# flyback_sematik.net
KiCad netlist of a schematic drawn in Altium Designer
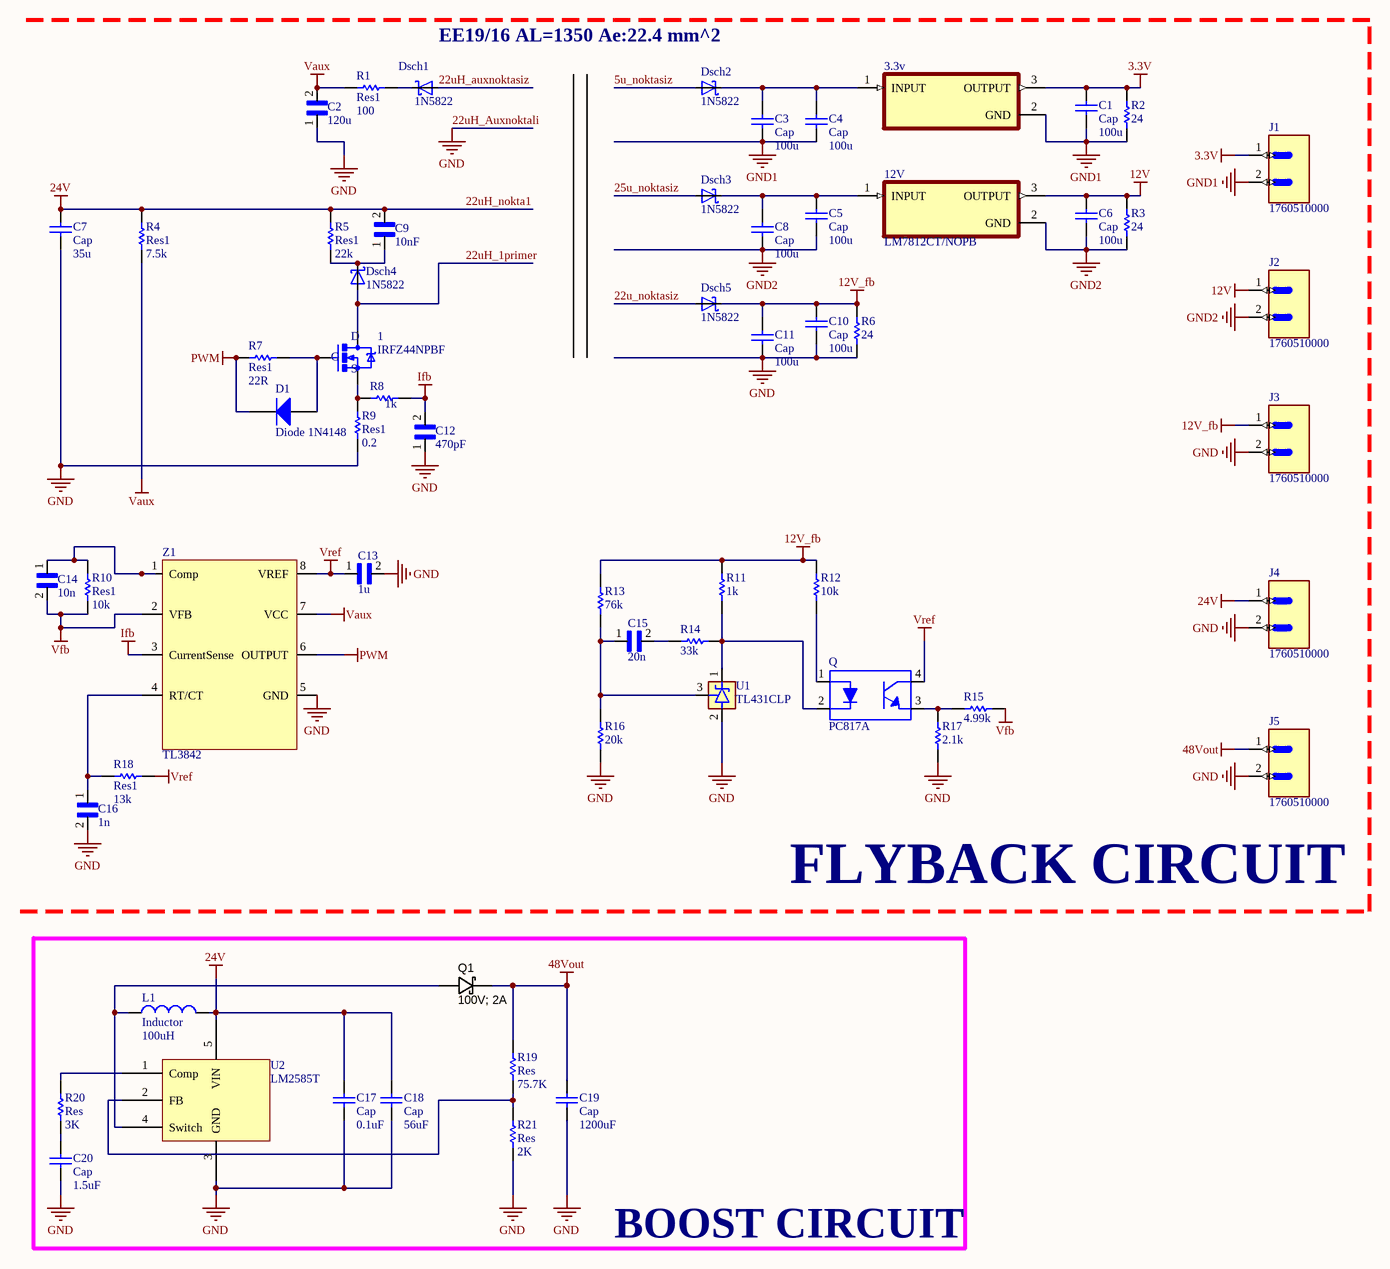
[diagram p0: flyback_sematik.SchDoc]

(export (version "E")
  (design (tool "Eeschema 10.0.6"))
  (components
    (comp (ref "1")
      (value "IRFZ44NPBF")
      (footprint "TO-220")
      (fields (field (name "MF") "Infineon"))
      (libsource (lib "IRFZ44NPBF") (part "IRFZ44NPBF"))
    )
    (comp (ref "3.3v")
      (value "LM7812CT/NOPB")
      (footprint "TO254P1054X470X1955-3")
      (description "1.5-A, 30-V, linear voltage regulator 3-TO-220 -40 to 125")
      (fields (field (name "MF") "Texas Instruments"))
      (libsource (lib "LM7812CT_NOPB") (part "LM7812CT/NOPB"))
    )
    (comp (ref "12V")
      (value "LM7812CT/NOPB")
      (footprint "TO254P1054X470X1955-3")
      (description "1.5-A, 30-V, linear voltage regulator 3-TO-220 -40 to 125")
      (fields (field (name "MF") "Texas Instruments"))
      (libsource (lib "LM7812CT_NOPB") (part "LM7812CT/NOPB"))
    )
    (comp (ref "C1")
      (value "Cap")
      (footprint "Cap1")
      (description "Capacitor")
      (fields (field (name "ALTIUM_VALUE") "100u") (field (name "PUBLISHER") "Altium Limited"))
      (libsource (lib "Miscellaneous Devices") (part "Cap"))
    )
    (comp (ref "C2")
      (value "120u")
      (footprint "CAP_RCER72A472K0A2H03B")
      (description "Cap Ceramic 1pF 50V C0G 0.25pF Radial 2.5mm 125C Automotive Bulk")
      (fields (field (name "MP") "RCER72A472K0A2H03B"))
      (libsource (lib "") (part "RCER72A472K0A2H03B_1"))
    )
    (comp (ref "C3")
      (value "Cap")
      (footprint "Cap1")
      (description "Capacitor")
      (fields (field (name "ALTIUM_VALUE") "100u") (field (name "PUBLISHER") "Altium Limited"))
      (libsource (lib "Miscellaneous Devices") (part "Cap"))
    )
    (comp (ref "C4")
      (value "Cap")
      (footprint "Cap1")
      (description "Capacitor")
      (fields (field (name "ALTIUM_VALUE") "100u") (field (name "PUBLISHER") "Altium Limited"))
      (libsource (lib "Miscellaneous Devices") (part "Cap"))
    )
    (comp (ref "C5")
      (value "Cap")
      (footprint "Cap1")
      (description "Capacitor")
      (fields (field (name "ALTIUM_VALUE") "100u") (field (name "PUBLISHER") "Altium Limited"))
      (libsource (lib "Miscellaneous Devices") (part "Cap"))
    )
    (comp (ref "C6")
      (value "Cap")
      (footprint "Cap1")
      (description "Capacitor")
      (fields (field (name "ALTIUM_VALUE") "100u") (field (name "PUBLISHER") "Altium Limited"))
      (libsource (lib "Miscellaneous Devices") (part "Cap"))
    )
    (comp (ref "C7")
      (value "Cap")
      (footprint "Cap1")
      (description "Capacitor")
      (fields (field (name "ALTIUM_VALUE") "35u") (field (name "PUBLISHER") "Altium Limited"))
      (libsource (lib "Miscellaneous Devices") (part "Cap"))
    )
    (comp (ref "C8")
      (value "Cap")
      (footprint "Cap1")
      (description "Capacitor")
      (fields (field (name "ALTIUM_VALUE") "100u") (field (name "PUBLISHER") "Altium Limited"))
      (libsource (lib "Miscellaneous Devices") (part "Cap"))
    )
    (comp (ref "C9")
      (value "10nF")
      (footprint "CAP_RCER72A472K0A2H03B")
      (description "Cap Ceramic 1pF 50V C0G 0.25pF Radial 2.5mm 125C Automotive Bulk")
      (fields (field (name "MP") "RCER72A472K0A2H03B"))
      (libsource (lib "") (part "RCER72A472K0A2H03B_1"))
    )
    (comp (ref "C10")
      (value "Cap")
      (footprint "Cap1")
      (description "Capacitor")
      (fields (field (name "ALTIUM_VALUE") "100u") (field (name "PUBLISHER") "Altium Limited"))
      (libsource (lib "Miscellaneous Devices") (part "Cap"))
    )
    (comp (ref "C11")
      (value "Cap")
      (footprint "Cap1")
      (description "Capacitor")
      (fields (field (name "ALTIUM_VALUE") "100u") (field (name "PUBLISHER") "Altium Limited"))
      (libsource (lib "Miscellaneous Devices") (part "Cap"))
    )
    (comp (ref "C12")
      (value "470pF")
      (footprint "CAP_RCER72A472K0A2H03B")
      (description "Cap Ceramic 1pF 50V C0G 0.25pF Radial 2.5mm 125C Automotive Bulk")
      (fields (field (name "MP") "RCER72A472K0A2H03B"))
      (libsource (lib "") (part "RCER72A472K0A2H03B_1"))
    )
    (comp (ref "C13")
      (value "1u")
      (footprint "CAP_RCER72A472K0A2H03B")
      (description "Cap Ceramic 1pF 50V C0G 0.25pF Radial 2.5mm 125C Automotive Bulk")
      (fields (field (name "MP") "RCER72A472K0A2H03B"))
      (libsource (lib "RCER72A472K0A2H03B") (part "RCER72A472K0A2H03B"))
    )
    (comp (ref "C14")
      (value "10n")
      (footprint "CAP_RCER72A472K0A2H03B")
      (description "Cap Ceramic 1pF 50V C0G 0.25pF Radial 2.5mm 125C Automotive Bulk")
      (fields (field (name "MP") "RCER72A472K0A2H03B"))
      (libsource (lib "") (part "RCER72A472K0A2H03B_2"))
    )
    (comp (ref "C15")
      (value "20n")
      (footprint "CAP_RCER72A472K0A2H03B")
      (description "Cap Ceramic 1pF 50V C0G 0.25pF Radial 2.5mm 125C Automotive Bulk")
      (fields (field (name "MP") "RCER72A472K0A2H03B"))
      (libsource (lib "RCER72A472K0A2H03B") (part "RCER72A472K0A2H03B"))
    )
    (comp (ref "C16")
      (value "1n")
      (footprint "CAP_RCER72A472K0A2H03B")
      (description "Cap Ceramic 1pF 50V C0G 0.25pF Radial 2.5mm 125C Automotive Bulk")
      (fields (field (name "MP") "RCER72A472K0A2H03B"))
      (libsource (lib "") (part "RCER72A472K0A2H03B_2"))
    )
    (comp (ref "C17")
      (value "Cap")
      (footprint "Cap1")
      (description "Capacitor")
      (fields (field (name "ALTIUM_VALUE") "0.1uF") (field (name "PUBLISHER") "Altium Limited"))
      (libsource (lib "Miscellaneous Devices") (part "Cap"))
    )
    (comp (ref "C18")
      (value "Cap")
      (footprint "Cap1")
      (description "Capacitor")
      (fields (field (name "ALTIUM_VALUE") "56uF") (field (name "PUBLISHER") "Altium Limited"))
      (libsource (lib "Miscellaneous Devices") (part "Cap"))
    )
    (comp (ref "C19")
      (value "Cap")
      (footprint "Cap1")
      (description "Capacitor")
      (fields (field (name "ALTIUM_VALUE") "1200uF") (field (name "PUBLISHER") "Altium Limited"))
      (libsource (lib "Miscellaneous Devices") (part "Cap"))
    )
    (comp (ref "C20")
      (value "Cap")
      (footprint "Cap1")
      (description "Capacitor")
      (fields (field (name "ALTIUM_VALUE") "1.5uF") (field (name "PUBLISHER") "Altium Limited"))
      (libsource (lib "Miscellaneous Devices") (part "Cap"))
    )
    (comp (ref "D1")
      (value "Diode 1N4148")
      (footprint "DO-35")
      (description "High Conductance Fast Diode")
      (fields (field (name "PUBLISHER") "Altium Limited"))
      (libsource (lib "Miscellaneous Devices") (part "Diode 1N4148"))
    )
    (comp (ref "Dsch1")
      (value "1N5822")
      (footprint "DIOAD2120W130L950D530P")
      (description "Diode Schottky 40V 3A Through Hole")
      (fields (field (name "MF") "ON Semiconductor"))
      (libsource (lib "1N5822") (part "1N5822"))
    )
    (comp (ref "Dsch2")
      (value "1N5822")
      (footprint "DIOAD2120W130L950D530P")
      (description "Diode Schottky 40V 3A Through Hole")
      (fields (field (name "MF") "ON Semiconductor"))
      (libsource (lib "1N5822") (part "1N5822"))
    )
    (comp (ref "Dsch3")
      (value "1N5822")
      (footprint "DIOAD2120W130L950D530P")
      (description "Diode Schottky 40V 3A Through Hole")
      (fields (field (name "MF") "ON Semiconductor"))
      (libsource (lib "1N5822") (part "1N5822"))
    )
    (comp (ref "Dsch4")
      (value "1N5822")
      (footprint "DIOAD2120W130L950D530P")
      (description "Diode Schottky 40V 3A Through Hole")
      (fields (field (name "MF") "ON Semiconductor"))
      (libsource (lib "1N5822") (part "1N5822"))
    )
    (comp (ref "Dsch5")
      (value "1N5822")
      (footprint "DIOAD2120W130L950D530P")
      (description "Diode Schottky 40V 3A Through Hole")
      (fields (field (name "MF") "ON Semiconductor"))
      (libsource (lib "1N5822") (part "1N5822"))
    )
    (comp (ref "J1")
      (value "1760510000")
      (footprint "1760490000")
      (description "2 Position Wire to Board Terminal Block Horizontal with Board 0.200 _5.08mm_ Through Hole")
      (fields (field (name "MF") "Weidmuller"))
      (libsource (lib "1760510000") (part "1760510000"))
    )
    (comp (ref "J2")
      (value "1760510000")
      (footprint "1760490000")
      (description "2 Position Wire to Board Terminal Block Horizontal with Board 0.200 _5.08mm_ Through Hole")
      (fields (field (name "MF") "Weidmuller"))
      (libsource (lib "1760510000") (part "1760510000"))
    )
    (comp (ref "J3")
      (value "1760510000")
      (footprint "1760490000")
      (description "2 Position Wire to Board Terminal Block Horizontal with Board 0.200 _5.08mm_ Through Hole")
      (fields (field (name "MF") "Weidmuller"))
      (libsource (lib "1760510000") (part "1760510000"))
    )
    (comp (ref "J4")
      (value "1760510000")
      (footprint "1760490000")
      (description "2 Position Wire to Board Terminal Block Horizontal with Board 0.200 _5.08mm_ Through Hole")
      (fields (field (name "MF") "Weidmuller"))
      (libsource (lib "1760510000") (part "1760510000"))
    )
    (comp (ref "J5")
      (value "1760510000")
      (footprint "1760490000")
      (description "2 Position Wire to Board Terminal Block Horizontal with Board 0.200 _5.08mm_ Through Hole")
      (fields (field (name "MF") "Weidmuller"))
      (libsource (lib "1760510000") (part "1760510000"))
    )
    (comp (ref "L1")
      (value "Inductor")
      (footprint "Inductor2")
      (fields (field (name "ALTIUM_VALUE") "100uH") (field (name "PUBLISHER") "Altium Limited"))
      (libsource (lib "Miscellaneous Devices") (part "Inductor"))
    )
    (comp (ref "Q")
      (value "PC817A")
      (footprint "DIP762W50P254L650H458Q4B")
      (description "Optoisolator Transistor Output 5000Vrms 1 Channel 4-DIP")
      (fields (field (name "MF") "Taiwan Semiconductor"))
      (libsource (lib "PC817A") (part "PC817A"))
    )
    (comp (ref "Q1")
      (value "DIODE_SCHOTTKY_10MQ100NPBF")
      (footprint "Schottky")
      (description "Diode Schottky SMD 100V 2A SMA")
      (fields (field (name "RATINGS") "100V; 2A"))
      (libsource (lib "PBL - Diodes") (part "DIODE_SCHOTTKY_10MQ100NPBF"))
    )
    (comp (ref "R1")
      (value "Res1")
      (footprint "AXIAL-0.3")
      (description "Resistor")
      (fields (field (name "ALTIUM_VALUE") "100") (field (name "PUBLISHER") "Altium Limited"))
      (libsource (lib "Miscellaneous Devices") (part "Res1"))
    )
    (comp (ref "R2")
      (value "24")
      (footprint "AXIAL-0.3")
      (description "Resistor")
      (fields (field (name "Comment") "Res1") (field (name "PUBLISHER") "Altium Limited"))
      (libsource (lib "Miscellaneous Devices") (part "Res1"))
    )
    (comp (ref "R3")
      (value "24")
      (footprint "AXIAL-0.3")
      (description "Resistor")
      (fields (field (name "Comment") "Res1") (field (name "PUBLISHER") "Altium Limited"))
      (libsource (lib "Miscellaneous Devices") (part "Res1"))
    )
    (comp (ref "R4")
      (value "Res1")
      (footprint "AXIAL-0.3")
      (description "Resistor")
      (fields (field (name "ALTIUM_VALUE") "7.5k") (field (name "PUBLISHER") "Altium Limited"))
      (libsource (lib "Miscellaneous Devices") (part "Res1"))
    )
    (comp (ref "R5")
      (value "Res1")
      (footprint "AXIAL-0.3")
      (description "Resistor")
      (fields (field (name "ALTIUM_VALUE") "22k") (field (name "PUBLISHER") "Altium Limited"))
      (libsource (lib "Miscellaneous Devices") (part "Res1"))
    )
    (comp (ref "R6")
      (value "24")
      (footprint "AXIAL-0.3")
      (description "Resistor")
      (fields (field (name "Comment") "Res1") (field (name "PUBLISHER") "Altium Limited"))
      (libsource (lib "Miscellaneous Devices") (part "Res1"))
    )
    (comp (ref "R7")
      (value "Res1")
      (footprint "AXIAL-0.3")
      (description "Resistor")
      (fields (field (name "ALTIUM_VALUE") "22R") (field (name "PUBLISHER") "Altium Limited"))
      (libsource (lib "Miscellaneous Devices") (part "Res1"))
    )
    (comp (ref "R8")
      (value "1k")
      (footprint "AXIAL-0.3")
      (description "Resistor")
      (fields (field (name "Comment") "Res1") (field (name "PUBLISHER") "Altium Limited"))
      (libsource (lib "Miscellaneous Devices") (part "Res1"))
    )
    (comp (ref "R9")
      (value "Res1")
      (footprint "AXIAL-0.3")
      (description "Resistor")
      (fields (field (name "ALTIUM_VALUE") "0.2") (field (name "PUBLISHER") "Altium Limited"))
      (libsource (lib "Miscellaneous Devices") (part "Res1"))
    )
    (comp (ref "R10")
      (value "Res1")
      (footprint "AXIAL-0.3")
      (description "Resistor")
      (fields (field (name "ALTIUM_VALUE") "10k") (field (name "PUBLISHER") "Altium Limited"))
      (libsource (lib "Miscellaneous Devices") (part "Res1"))
    )
    (comp (ref "R11")
      (value "1k")
      (footprint "AXIAL-0.3")
      (description "Resistor")
      (fields (field (name "Comment") "Res1") (field (name "PUBLISHER") "Altium Limited"))
      (libsource (lib "Miscellaneous Devices") (part "Res1"))
    )
    (comp (ref "R12")
      (value "10k")
      (footprint "AXIAL-0.3")
      (description "Resistor")
      (fields (field (name "Comment") "Res1") (field (name "PUBLISHER") "Altium Limited"))
      (libsource (lib "Miscellaneous Devices") (part "Res1"))
    )
    (comp (ref "R13")
      (value "76k")
      (footprint "AXIAL-0.3")
      (description "Resistor")
      (fields (field (name "Comment") "Res1") (field (name "PUBLISHER") "Altium Limited"))
      (libsource (lib "Miscellaneous Devices") (part "Res1"))
    )
    (comp (ref "R14")
      (value "33k")
      (footprint "AXIAL-0.3")
      (description "Resistor")
      (fields (field (name "Comment") "Res1") (field (name "PUBLISHER") "Altium Limited"))
      (libsource (lib "Miscellaneous Devices") (part "Res1"))
    )
    (comp (ref "R15")
      (value "4.99k")
      (footprint "AXIAL-0.3")
      (description "Resistor")
      (fields (field (name "Comment") "Res1") (field (name "PUBLISHER") "Altium Limited"))
      (libsource (lib "Miscellaneous Devices") (part "Res1"))
    )
    (comp (ref "R16")
      (value "20k")
      (footprint "AXIAL-0.3")
      (description "Resistor")
      (fields (field (name "Comment") "Res1") (field (name "PUBLISHER") "Altium Limited"))
      (libsource (lib "Miscellaneous Devices") (part "Res1"))
    )
    (comp (ref "R17")
      (value "2.1k")
      (footprint "AXIAL-0.3")
      (description "Resistor")
      (fields (field (name "Comment") "Res1") (field (name "PUBLISHER") "Altium Limited"))
      (libsource (lib "Miscellaneous Devices") (part "Res1"))
    )
    (comp (ref "R18")
      (value "Res1")
      (footprint "AXIAL-0.3")
      (description "Resistor")
      (fields (field (name "ALTIUM_VALUE") "13k") (field (name "PUBLISHER") "Altium Limited"))
      (libsource (lib "Miscellaneous Devices") (part "Res1"))
    )
    (comp (ref "R19")
      (value "Res")
      (footprint "AXIAL-0.3")
      (description "Resistor")
      (fields (field (name "ALTIUM_VALUE") "75.7K") (field (name "PUBLISHER") "Altium Limited"))
      (libsource (lib "Miscellaneous Devices") (part "Res1"))
    )
    (comp (ref "R20")
      (value "Res")
      (footprint "AXIAL-0.3")
      (description "Resistor")
      (fields (field (name "ALTIUM_VALUE") "3K") (field (name "PUBLISHER") "Altium Limited"))
      (libsource (lib "Miscellaneous Devices") (part "Res1"))
    )
    (comp (ref "R21")
      (value "Res")
      (footprint "AXIAL-0.3")
      (description "Resistor")
      (fields (field (name "ALTIUM_VALUE") "2K") (field (name "PUBLISHER") "Altium Limited"))
      (libsource (lib "Miscellaneous Devices") (part "Res1"))
    )
    (comp (ref "U1")
      (value "TL431CLP")
      (footprint "TO-92")
      (description "Adjustable precision shunt regulator 3-TO-92 0 to 70")
      (fields (field (name "MF") "Texas Instruments"))
      (libsource (lib "TL431CLP") (part "TL431CLP"))
    )
    (comp (ref "U2") (value "LM2585T") (footprint "LM2585T") (libsource (lib "LM2585T") (part "LM2585T")))
    (comp (ref "Z1")
      (value "TL3842")
      (footprint "TL3842_PCBLIB")
      (libsource (lib "TL3842_schematicLib") (part "TL3842"))
    )
  )
  (nets
    (net (code "1") (name "/5u_noktasiz") (class "Default")
      (node (ref "Dsch2") (pin "A") (pinfunction "A_A") (pintype "passive"))
    )
    (net (code "2") (name "/22uH_1primer") (class "Default")
      (node (ref "1") (pin "2") (pinfunction "D_2") (pintype "passive"))
      (node (ref "Dsch4") (pin "A") (pinfunction "A_A") (pintype "passive"))
    )
    (net (code "3") (name "/22uH_auxnoktasiz") (class "Default")
      (node (ref "Dsch1") (pin "A") (pinfunction "A_A") (pintype "passive"))
    )
    (net (code "4") (name "/22u_noktasiz") (class "Default")
      (node (ref "Dsch5") (pin "A") (pinfunction "A_A") (pintype "passive"))
    )
    (net (code "5") (name "/25u_noktasiz") (class "Default")
      (node (ref "Dsch3") (pin "A") (pinfunction "A_A") (pintype "passive"))
    )
    (net (code "6") (name "3.3V") (class "Default")
      (node (ref "3.3v") (pin "3") (pinfunction "OUTPUT_3") (pintype "output"))
      (node (ref "C1") (pin "1") (pinfunction "1_1") (pintype "passive"))
      (node (ref "J1") (pin "1") (pinfunction "1_1") (pintype "bidirectional"))
      (node (ref "R2") (pin "2") (pinfunction "2_2") (pintype "passive"))
    )
    (net (code "7") (name "12V") (class "Default")
      (node (ref "12V") (pin "3") (pinfunction "OUTPUT_3") (pintype "output"))
      (node (ref "C6") (pin "1") (pinfunction "1_1") (pintype "passive"))
      (node (ref "J2") (pin "1") (pinfunction "1_1") (pintype "bidirectional"))
      (node (ref "R3") (pin "2") (pinfunction "2_2") (pintype "passive"))
    )
    (net (code "8") (name "12V_fb") (class "Default")
      (node (ref "C10") (pin "1") (pinfunction "1_1") (pintype "passive"))
      (node (ref "C11") (pin "1") (pinfunction "1_1") (pintype "passive"))
      (node (ref "Dsch5") (pin "C") (pinfunction "C_C") (pintype "passive"))
      (node (ref "J3") (pin "1") (pinfunction "1_1") (pintype "bidirectional"))
      (node (ref "R11") (pin "2") (pinfunction "2_2") (pintype "passive"))
      (node (ref "R12") (pin "2") (pinfunction "2_2") (pintype "passive"))
      (node (ref "R13") (pin "2") (pinfunction "2_2") (pintype "passive"))
      (node (ref "R6") (pin "2") (pinfunction "2_2") (pintype "passive"))
    )
    (net (code "9") (name "24V") (class "Default")
      (node (ref "C17") (pin "1") (pinfunction "1_1") (pintype "passive"))
      (node (ref "C18") (pin "1") (pinfunction "1_1") (pintype "passive"))
      (node (ref "C7") (pin "1") (pinfunction "1_1") (pintype "passive"))
      (node (ref "C9") (pin "2") (pinfunction "2_2") (pintype "passive"))
      (node (ref "J4") (pin "1") (pinfunction "1_1") (pintype "bidirectional"))
      (node (ref "L1") (pin "2") (pinfunction "2_2") (pintype "passive"))
      (node (ref "R4") (pin "1") (pinfunction "1_1") (pintype "passive"))
      (node (ref "R5") (pin "1") (pinfunction "1_1") (pintype "passive"))
      (node (ref "U2") (pin "5") (pinfunction "VIN_5") (pintype "passive"))
    )
    (net (code "10") (name "48Vout") (class "Default")
      (node (ref "C19") (pin "1") (pinfunction "1_1") (pintype "passive"))
      (node (ref "J5") (pin "1") (pinfunction "1_1") (pintype "bidirectional"))
      (node (ref "Q1") (pin "2") (pinfunction "2_2") (pintype "passive"))
      (node (ref "R19") (pin "2") (pinfunction "2_2") (pintype "passive"))
    )
    (net (code "11") (name "GND") (class "Default")
      (node (ref "C10") (pin "2") (pinfunction "2_2") (pintype "passive"))
      (node (ref "C11") (pin "2") (pinfunction "2_2") (pintype "passive"))
      (node (ref "C12") (pin "1") (pinfunction "1_1") (pintype "passive"))
      (node (ref "C13") (pin "2") (pinfunction "2_2") (pintype "passive"))
      (node (ref "C16") (pin "2") (pinfunction "2_2") (pintype "passive"))
      (node (ref "C17") (pin "2") (pinfunction "2_2") (pintype "passive"))
      (node (ref "C18") (pin "2") (pinfunction "2_2") (pintype "passive"))
      (node (ref "C19") (pin "2") (pinfunction "2_2") (pintype "passive"))
      (node (ref "C2") (pin "1") (pinfunction "1_1") (pintype "passive"))
      (node (ref "C20") (pin "2") (pinfunction "2_2") (pintype "passive"))
      (node (ref "C7") (pin "2") (pinfunction "2_2") (pintype "passive"))
      (node (ref "J3") (pin "2") (pinfunction "2_2") (pintype "bidirectional"))
      (node (ref "J4") (pin "2") (pinfunction "2_2") (pintype "bidirectional"))
      (node (ref "J5") (pin "2") (pinfunction "2_2") (pintype "bidirectional"))
      (node (ref "R16") (pin "1") (pinfunction "1_1") (pintype "passive"))
      (node (ref "R17") (pin "2") (pinfunction "2_2") (pintype "passive"))
      (node (ref "R21") (pin "1") (pinfunction "1_1") (pintype "passive"))
      (node (ref "R6") (pin "1") (pinfunction "1_1") (pintype "passive"))
      (node (ref "R9") (pin "2") (pinfunction "2_2") (pintype "passive"))
      (node (ref "U1") (pin "2") (pinfunction "ANODE_2") (pintype "passive"))
      (node (ref "U2") (pin "3") (pinfunction "GND_3") (pintype "passive"))
      (node (ref "Z1") (pin "5") (pinfunction "GND_5") (pintype "passive"))
    )
    (net (code "12") (name "GND1") (class "Default")
      (node (ref "3.3v") (pin "2") (pinfunction "GND_2") (pintype "power_in"))
      (node (ref "C1") (pin "2") (pinfunction "2_2") (pintype "passive"))
      (node (ref "C3") (pin "2") (pinfunction "2_2") (pintype "passive"))
      (node (ref "C4") (pin "2") (pinfunction "2_2") (pintype "passive"))
      (node (ref "J1") (pin "2") (pinfunction "2_2") (pintype "bidirectional"))
      (node (ref "R2") (pin "1") (pinfunction "1_1") (pintype "passive"))
    )
    (net (code "13") (name "GND2") (class "Default")
      (node (ref "12V") (pin "2") (pinfunction "GND_2") (pintype "power_in"))
      (node (ref "C5") (pin "2") (pinfunction "2_2") (pintype "passive"))
      (node (ref "C6") (pin "2") (pinfunction "2_2") (pintype "passive"))
      (node (ref "C8") (pin "2") (pinfunction "2_2") (pintype "passive"))
      (node (ref "J2") (pin "2") (pinfunction "2_2") (pintype "bidirectional"))
      (node (ref "R3") (pin "1") (pinfunction "1_1") (pintype "passive"))
    )
    (net (code "14") (name "Ifb") (class "Default")
      (node (ref "C12") (pin "2") (pinfunction "2_2") (pintype "passive"))
      (node (ref "R8") (pin "2") (pinfunction "2_2") (pintype "passive"))
      (node (ref "Z1") (pin "3") (pinfunction "CurrentSense_3") (pintype "passive"))
    )
    (net (code "15") (name "Net-(1-G)") (class "Default")
      (node (ref "1") (pin "1") (pinfunction "G_1") (pintype "passive"))
      (node (ref "D1") (pin "1") (pinfunction "A_1") (pintype "passive"))
      (node (ref "R7") (pin "2") (pinfunction "2_2") (pintype "passive"))
    )
    (net (code "16") (name "Net-(1-S)") (class "Default")
      (node (ref "1") (pin "3") (pinfunction "S_3") (pintype "passive"))
      (node (ref "R8") (pin "1") (pinfunction "1_1") (pintype "passive"))
      (node (ref "R9") (pin "1") (pinfunction "1_1") (pintype "passive"))
    )
    (net (code "17") (name "Net-(3.3v-INPUT)") (class "Default")
      (node (ref "3.3v") (pin "1") (pinfunction "INPUT_1") (pintype "input"))
      (node (ref "C3") (pin "1") (pinfunction "1_1") (pintype "passive"))
      (node (ref "C4") (pin "1") (pinfunction "1_1") (pintype "passive"))
      (node (ref "Dsch2") (pin "C") (pinfunction "C_C") (pintype "passive"))
    )
    (net (code "18") (name "Net-(12V-INPUT)") (class "Default")
      (node (ref "12V") (pin "1") (pinfunction "INPUT_1") (pintype "input"))
      (node (ref "C5") (pin "1") (pinfunction "1_1") (pintype "passive"))
      (node (ref "C8") (pin "1") (pinfunction "1_1") (pintype "passive"))
      (node (ref "Dsch3") (pin "C") (pinfunction "C_C") (pintype "passive"))
    )
    (net (code "19") (name "Net-(C9-Pad1)") (class "Default")
      (node (ref "C9") (pin "1") (pinfunction "1_1") (pintype "passive"))
      (node (ref "Dsch4") (pin "C") (pinfunction "C_C") (pintype "passive"))
      (node (ref "R5") (pin "2") (pinfunction "2_2") (pintype "passive"))
    )
    (net (code "20") (name "Net-(C15-Pad2)") (class "Default")
      (node (ref "C15") (pin "2") (pinfunction "2_2") (pintype "passive"))
      (node (ref "R14") (pin "2") (pinfunction "2_2") (pintype "passive"))
    )
    (net (code "21") (name "Net-(C20-Pad1)") (class "Default")
      (node (ref "C20") (pin "1") (pinfunction "1_1") (pintype "passive"))
      (node (ref "R20") (pin "1") (pinfunction "1_1") (pintype "passive"))
    )
    (net (code "22") (name "Net-(Dsch1-PadC)") (class "Default")
      (node (ref "Dsch1") (pin "C") (pinfunction "C_C") (pintype "passive"))
      (node (ref "R1") (pin "1") (pinfunction "1_1") (pintype "passive"))
    )
    (net (code "23") (name "Net-(Q-Pad1)") (class "Default")
      (node (ref "Q") (pin "1") (pinfunction "1_1") (pintype "passive"))
      (node (ref "R12") (pin "1") (pinfunction "1_1") (pintype "passive"))
    )
    (net (code "24") (name "Net-(Q-Pad3)") (class "Default")
      (node (ref "Q") (pin "3") (pinfunction "3_3") (pintype "passive"))
      (node (ref "R15") (pin "2") (pinfunction "2_2") (pintype "passive"))
      (node (ref "R17") (pin "1") (pinfunction "1_1") (pintype "passive"))
    )
    (net (code "25") (name "Net-(U1-CATHODE)") (class "Default")
      (node (ref "Q") (pin "2") (pinfunction "2_2") (pintype "passive"))
      (node (ref "R11") (pin "1") (pinfunction "1_1") (pintype "passive"))
      (node (ref "R14") (pin "1") (pinfunction "1_1") (pintype "passive"))
      (node (ref "U1") (pin "1") (pinfunction "CATHODE_1") (pintype "passive"))
    )
    (net (code "26") (name "Net-(U1-REF)") (class "Default")
      (node (ref "C15") (pin "1") (pinfunction "1_1") (pintype "passive"))
      (node (ref "R13") (pin "1") (pinfunction "1_1") (pintype "passive"))
      (node (ref "R16") (pin "2") (pinfunction "2_2") (pintype "passive"))
      (node (ref "U1") (pin "3") (pinfunction "REF_3") (pintype "passive"))
    )
    (net (code "27") (name "Net-(U2-Comp)") (class "Default")
      (node (ref "R20") (pin "2") (pinfunction "2_2") (pintype "passive"))
      (node (ref "U2") (pin "1") (pinfunction "Comp_1") (pintype "passive"))
    )
    (net (code "28") (name "Net-(U2-FB)") (class "Default")
      (node (ref "R19") (pin "1") (pinfunction "1_1") (pintype "passive"))
      (node (ref "R21") (pin "2") (pinfunction "2_2") (pintype "passive"))
      (node (ref "U2") (pin "2") (pinfunction "FB_2") (pintype "passive"))
    )
    (net (code "29") (name "Net-(U2-Switch)") (class "Default")
      (node (ref "L1") (pin "1") (pinfunction "1_1") (pintype "passive"))
      (node (ref "Q1") (pin "1") (pinfunction "1_1") (pintype "passive"))
      (node (ref "U2") (pin "4") (pinfunction "Switch_4") (pintype "passive"))
    )
    (net (code "30") (name "Net-(Z1-Comp)") (class "Default")
      (node (ref "C14") (pin "1") (pinfunction "1_1") (pintype "passive"))
      (node (ref "R10") (pin "2") (pinfunction "2_2") (pintype "passive"))
      (node (ref "Z1") (pin "1") (pinfunction "Comp_1") (pintype "passive"))
    )
    (net (code "31") (name "Net-(Z1-RT{slash}CT)") (class "Default")
      (node (ref "C16") (pin "1") (pinfunction "1_1") (pintype "passive"))
      (node (ref "R18") (pin "1") (pinfunction "1_1") (pintype "passive"))
      (node (ref "Z1") (pin "4") (pinfunction "RT/CT_4") (pintype "passive"))
    )
    (net (code "32") (name "PWM") (class "Default")
      (node (ref "D1") (pin "2") (pinfunction "K_2") (pintype "passive"))
      (node (ref "R7") (pin "1") (pinfunction "1_1") (pintype "passive"))
      (node (ref "Z1") (pin "6") (pinfunction "OUTPUT_6") (pintype "passive"))
    )
    (net (code "33") (name "Vaux") (class "Default")
      (node (ref "C2") (pin "2") (pinfunction "2_2") (pintype "passive"))
      (node (ref "R1") (pin "2") (pinfunction "2_2") (pintype "passive"))
      (node (ref "R4") (pin "2") (pinfunction "2_2") (pintype "passive"))
      (node (ref "Z1") (pin "7") (pinfunction "VCC_7") (pintype "passive"))
    )
    (net (code "34") (name "Vfb") (class "Default")
      (node (ref "C14") (pin "2") (pinfunction "2_2") (pintype "passive"))
      (node (ref "R10") (pin "1") (pinfunction "1_1") (pintype "passive"))
      (node (ref "R15") (pin "1") (pinfunction "1_1") (pintype "passive"))
      (node (ref "Z1") (pin "2") (pinfunction "VFB_2") (pintype "passive"))
    )
    (net (code "35") (name "Vref") (class "Default")
      (node (ref "C13") (pin "1") (pinfunction "1_1") (pintype "passive"))
      (node (ref "Q") (pin "4") (pinfunction "4_4") (pintype "passive"))
      (node (ref "R18") (pin "2") (pinfunction "2_2") (pintype "passive"))
      (node (ref "Z1") (pin "8") (pinfunction "VREF_8") (pintype "passive"))
    )
  )
)
